# power-v5.net
KiCad netlist of a schematic drawn in Altium Designer
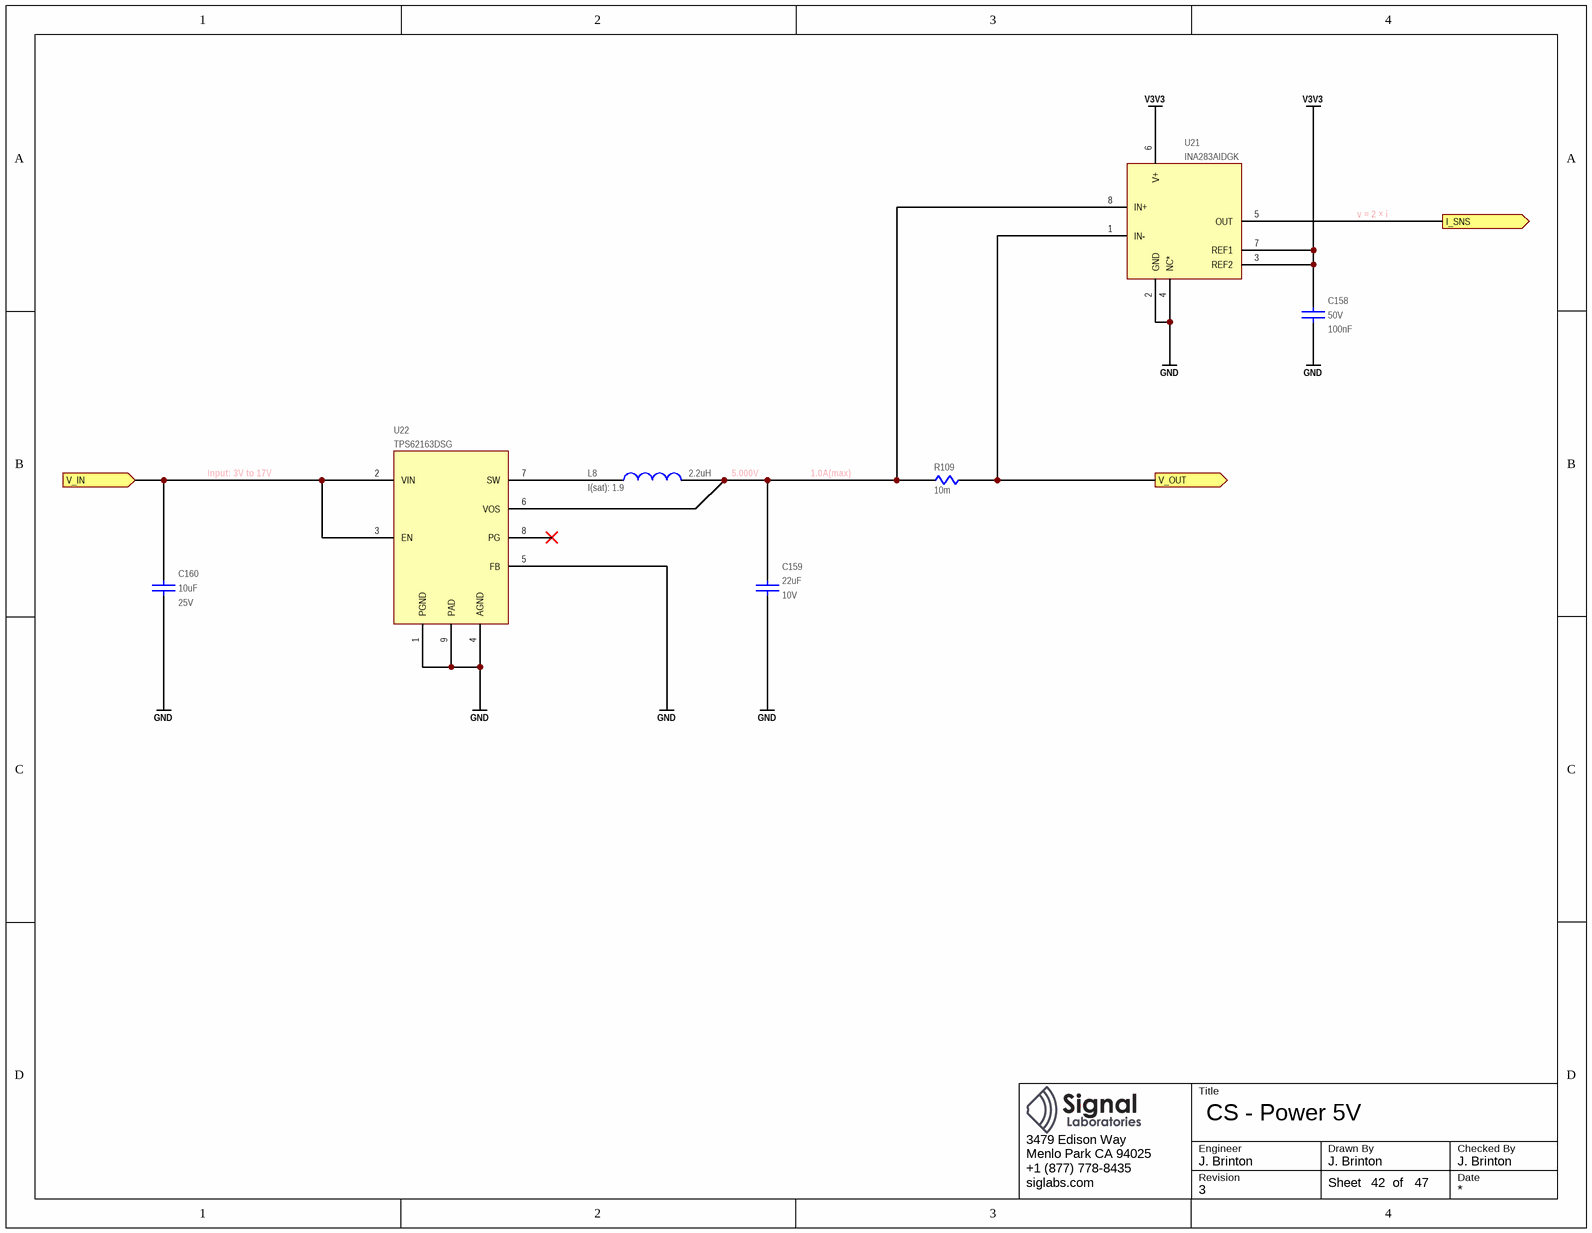
[diagram p0: power-v5.SchDoc]

(export (version "E")
  (design (tool "Eeschema 10.0.6"))
  (components
    (comp (ref "C158")
      (value "100nF")
      (footprint "CAPC100X50X55L25N")
      (description "Ceramic Capacitor 100nF ±10% 50V X7R 0402")
      (fields
        (field (name "MANUFACTURER") "Murata")
        (field (name "TOLERANCE") "±10%")
        (field (name "VOLTAGE") "50V")
      )
      (libsource (lib "generic") (part "CAP"))
    )
    (comp (ref "C159")
      (value "22uF")
      (footprint "CAPC200X125X145L45N")
      (description "Ceramic Capacitor 22uF ±20% 10V X7S 0805")
      (fields
        (field (name "MANUFACTURER") "TDK")
        (field (name "TOLERANCE") "±20%")
        (field (name "VOLTAGE") "10V")
      )
      (libsource (lib "") (part "CAP_1"))
    )
    (comp (ref "C160")
      (value "10uF")
      (footprint "CAPC200X125X145L45N")
      (description "Ceramic Capacitor 10uF ±10% 25V X6S 0805")
      (fields
        (field (name "MANUFACTURER") "Murata")
        (field (name "TOLERANCE") "±10%")
        (field (name "VOLTAGE") "25V")
      )
      (libsource (lib "generic") (part "CAP"))
    )
    (comp (ref "L8")
      (value "2.2uH")
      (footprint "ASPI-3010FS")
      (description "Wirewound Inductor 2.2uH +/-20% 1.9A SMD 2518")
      (fields
        (field (name "MANUFACTURER") "Abracon")
        (field (name "I(SAT)") "1.9")
        (field (name "Comment") "ASPI-0310FS-2R2M-T2")
      )
      (libsource (lib "CamBoard_Pico_70.19K") (part "COIL"))
    )
    (comp (ref "R109")
      (value "10m")
      (footprint "RESC3216X80L110N")
      (description "Current Sense Resistor 10mOhm +/-1% SMD 1206")
      (fields (field (name "MANUFACTURER") "Riedon") (field (name "Comment") "CSR1206-0R01F1"))
      (libsource (lib "Kron Library Rev 3") (part "CSR1206-0R001F1"))
    )
    (comp (ref "U21")
      (value "INA283AIDGK")
      (footprint "texas_instruments:S-PDSO-G8")
      (description "Bidirectional Current Shunt Monitor")
      (fields (field (name "MANUFACTURER") "Texas Instruments"))
      (libsource (lib "ti") (part "INA283AIDGK"))
    )
    (comp (ref "U22")
      (value "TPS62163DSG")
      (footprint "DSG")
      (description "1A Step-Down Converter, 5V")
      (fields (field (name "MANUFACTURER") "Texas Instruments"))
      (libsource (lib "ti") (part "TPS62163DSG"))
    )
  )
  (nets
    (net (code "1") (name "/I_SNS") (class "Default")
      (node (ref "U21") (pin "5") (pinfunction "OUT_5") (pintype "passive"))
    )
    (net (code "2") (name "/V_IN") (class "Default")
      (node (ref "C160") (pin "2") (pinfunction "2_2") (pintype "passive"))
      (node (ref "U22") (pin "2") (pinfunction "VIN_2") (pintype "passive"))
      (node (ref "U22") (pin "3") (pinfunction "EN_3") (pintype "passive"))
    )
    (net (code "3") (name "/V_OUT") (class "Default")
      (node (ref "R109") (pin "2") (pintype "passive"))
      (node (ref "U21") (pin "1") (pinfunction "IN-_1") (pintype "passive"))
    )
    (net (code "4") (name "GND") (class "Default")
      (node (ref "C158") (pin "1") (pinfunction "1_1") (pintype "passive"))
      (node (ref "C159") (pin "1") (pinfunction "1_1") (pintype "passive"))
      (node (ref "C160") (pin "1") (pinfunction "1_1") (pintype "passive"))
      (node (ref "U21") (pin "2") (pinfunction "GND_2") (pintype "passive"))
      (node (ref "U21") (pin "4") (pinfunction "NC*_4") (pintype "passive"))
      (node (ref "U22") (pin "1") (pinfunction "PGND_1") (pintype "passive"))
      (node (ref "U22") (pin "4") (pinfunction "AGND_4") (pintype "passive"))
      (node (ref "U22") (pin "5") (pinfunction "FB_5") (pintype "passive"))
      (node (ref "U22") (pin "9") (pinfunction "PAD_9") (pintype "passive"))
    )
    (net (code "5") (name "Net-(U21-IN+)") (class "Default")
      (node (ref "C159") (pin "2") (pinfunction "2_2") (pintype "passive"))
      (node (ref "L8") (pin "2") (pinfunction "2_2") (pintype "passive"))
      (node (ref "R109") (pin "1") (pintype "passive"))
      (node (ref "U21") (pin "8") (pinfunction "IN+_8") (pintype "passive"))
      (node (ref "U22") (pin "6") (pinfunction "VOS_6") (pintype "passive"))
    )
    (net (code "6") (name "Net-(U22-SW)") (class "Default")
      (node (ref "L8") (pin "1") (pinfunction "1_1") (pintype "passive"))
      (node (ref "U22") (pin "7") (pinfunction "SW_7") (pintype "passive"))
    )
    (net (code "7") (name "V3V3") (class "Default")
      (node (ref "C158") (pin "2") (pinfunction "2_2") (pintype "passive"))
      (node (ref "U21") (pin "3") (pinfunction "REF2_3") (pintype "passive"))
      (node (ref "U21") (pin "6") (pinfunction "V+_6") (pintype "passive"))
      (node (ref "U21") (pin "7") (pinfunction "REF1_7") (pintype "passive"))
    )
    (net (code "8") (name "unconnected-(U22-PG-Pad8)") (class "Default")
      (node (ref "U22") (pin "8") (pinfunction "PG_8") (pintype "passive+no_connect"))
    )
  )
)
